# LDO_3V3.net
KiCad netlist of a schematic drawn in Altium Designer
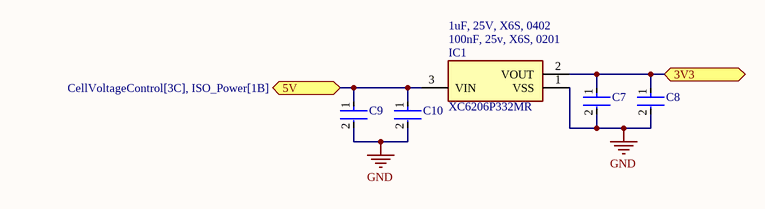
[diagram p0: LDO_3V3.SchDoc]

(export (version "E")
  (design (tool "Eeschema 10.0.6"))
  (components
    (comp (ref "C7")
      (value "100nF, 25v, X6S, 0201")
      (footprint "FP-GRM033-0_03-IPC_B")
      (description "Chip Multilayer Ceramic Capacitors for General Purpose, 0201, 0.10uF, X6S, 22%, 10%, 25V")
      (fields (field (name "TOLERANCE") "10%"))
      (libsource (lib "Altium Content Vault") (part "b4654b650e69147ec39a6b967a45e02"))
    )
    (comp (ref "C8")
      (value "1uF, 25V, X6S, 0402")
      (footprint "FP-GRT155-0_1-IPC_A")
      (description "Multi-Layer Ceramic Capacitor 1uF 25V X6S ±10% 0402 Paper T/R")
      (libsource (lib "Altium Content Vault") (part "02cd4be3c70576c341d710602a673aa"))
    )
    (comp (ref "C9")
      (value "1uF, 25V, X6S, 0402")
      (footprint "FP-GRT155-0_1-IPC_A")
      (description "Multi-Layer Ceramic Capacitor 1uF 25V X6S ±10% 0402 Paper T/R")
      (libsource (lib "Altium Content Vault") (part "02cd4be3c70576c341d710602a673aa"))
    )
    (comp (ref "C10")
      (value "100nF, 25v, X6S, 0201")
      (footprint "FP-GRM033-0_03-IPC_B")
      (description "Chip Multilayer Ceramic Capacitors for General Purpose, 0201, 0.10uF, X6S, 22%, 10%, 25V")
      (fields (field (name "TOLERANCE") "10%"))
      (libsource (lib "Altium Content Vault") (part "b4654b650e69147ec39a6b967a45e02"))
    )
    (comp (ref "IC1")
      (value "XC6206P332MR")
      (footprint "SamacSys:SOT95P280X130-3N")
      (description "Integrated Circuit")
      (libsource (lib "*") (part "XC6206P332MR"))
    )
  )
  (nets
    (net (code "1") (name "/3V3") (class "Default")
      (node (ref "C7") (pin "1") (pinfunction "1_1") (pintype "passive"))
      (node (ref "C8") (pin "1") (pinfunction "1_1") (pintype "passive"))
      (node (ref "IC1") (pin "2") (pinfunction "VOUT_2") (pintype "passive"))
    )
    (net (code "2") (name "/5V") (class "Default")
      (node (ref "C10") (pin "1") (pinfunction "1_1") (pintype "passive"))
      (node (ref "C9") (pin "1") (pinfunction "1_1") (pintype "passive"))
      (node (ref "IC1") (pin "3") (pinfunction "VIN_3") (pintype "passive"))
    )
    (net (code "3") (name "GND") (class "Default")
      (node (ref "C10") (pin "2") (pinfunction "2_2") (pintype "passive"))
      (node (ref "C7") (pin "2") (pinfunction "2_2") (pintype "passive"))
      (node (ref "C8") (pin "2") (pinfunction "2_2") (pintype "passive"))
      (node (ref "C9") (pin "2") (pinfunction "2_2") (pintype "passive"))
      (node (ref "IC1") (pin "1") (pinfunction "VSS_1") (pintype "passive"))
    )
  )
)
